# GR_Stepper_Driver.net
KiCad netlist of a schematic drawn in Altium Designer
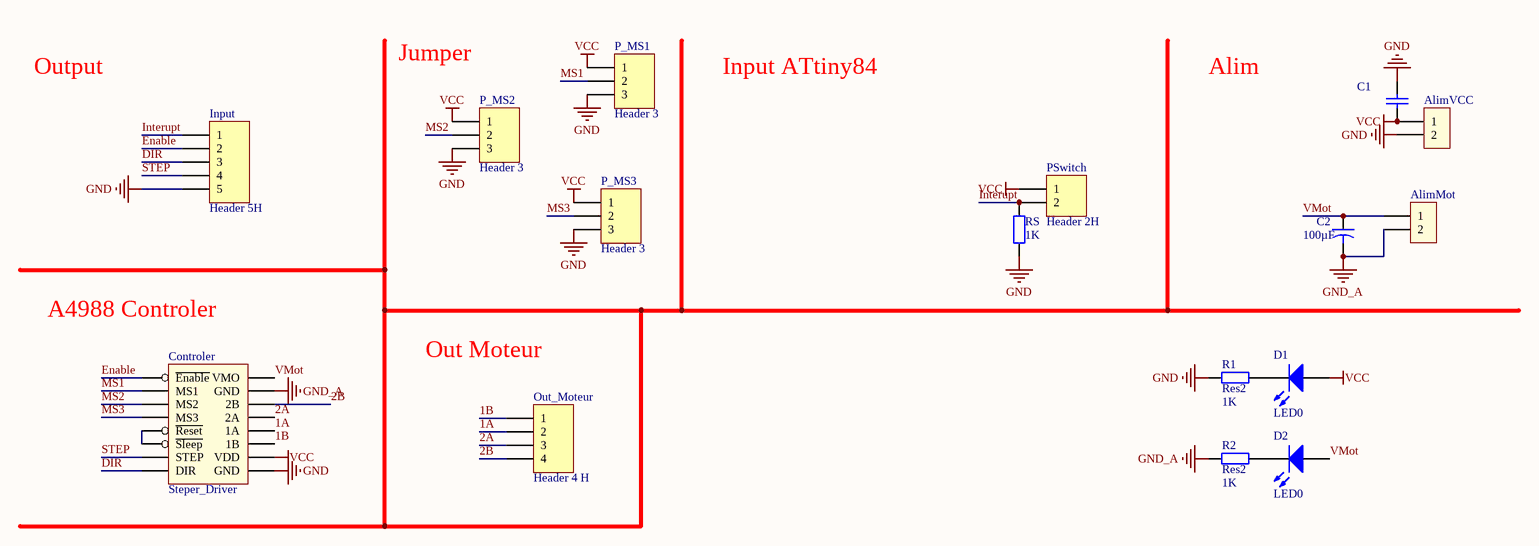
[diagram p0: GR_Stepper_Driver.SchDoc]

(export (version "E")
  (design (tool "Eeschema 10.0.6"))
  (components
    (comp (ref "AlimMot")
      (value "AlimMot")
      (footprint "Molex_MiniFitJr_2x1H")
      (libsource (lib "Robot_2019") (part "Molex_minifit_2"))
    )
    (comp (ref "AlimVCC")
      (value "AlimVCC")
      (footprint "Molex_MiniFitJr_2x1H")
      (libsource (lib "Robot_2019") (part "Molex_minifit_2"))
    )
    (comp (ref "C1")
      (value "Cap")
      (footprint "3.2X1.6X1.1")
      (description "Capacitor")
      (fields (field (name "PUBLISHER") "Altium Limited"))
      (libsource (lib "Miscellaneous Devices") (part "Cap"))
    )
    (comp (ref "C2")
      (value "100µF")
      (footprint "Robot_2019:Condensateur")
      (description "Capacitor")
      (fields (field (name "Comment") "Cap2") (field (name "PUBLISHER") "Altium Limited"))
      (libsource (lib "Miscellaneous Devices") (part "Cap2"))
    )
    (comp (ref "Controler")
      (value "Steper_Driver")
      (footprint "A4988_module")
      (description "A4988")
      (libsource (lib "Robot_2019") (part "Steper_Driver"))
    )
    (comp (ref "D1")
      (value "LED0")
      (footprint "3.2X1.6X1.1")
      (description "Typical INFRARED GaAs LED")
      (fields (field (name "PUBLISHER") "Altium Limited"))
      (libsource (lib "Miscellaneous Devices") (part "LED0"))
    )
    (comp (ref "D2")
      (value "LED0")
      (footprint "3.2X1.6X1.1")
      (description "Typical INFRARED GaAs LED")
      (fields (field (name "PUBLISHER") "Altium Limited"))
      (libsource (lib "Miscellaneous Devices") (part "LED0"))
    )
    (comp (ref "Input")
      (value "Header 5H")
      (footprint "MOLEX SPOX 5X1H")
      (description "Header, 5-Pin, Right Angle")
      (fields (field (name "PUBLISHER") "Altium Limited"))
      (libsource (lib "Miscellaneous Connectors") (part "Header 5H"))
    )
    (comp (ref "Out_Moteur")
      (value "Header 4 H")
      (footprint "Molex SPOX 4x1H")
      (description "Header, 4-Pin")
      (fields (field (name "PUBLISHER") "Altium Limited"))
      (libsource (lib "Miscellaneous Connectors") (part "Header 4"))
    )
    (comp (ref "PSwitch")
      (value "Header 2H")
      (footprint "Molex SPOX 2x1H")
      (description "Header, 2-Pin, Right Angle")
      (fields (field (name "PUBLISHER") "Altium Limited"))
      (libsource (lib "Miscellaneous Connectors") (part "Header 2H"))
    )
    (comp (ref "P_MS1")
      (value "Header 3")
      (footprint "HDR1X3")
      (description "Header, 3-Pin")
      (fields (field (name "PUBLISHER") "Altium Limited"))
      (libsource (lib "Miscellaneous Connectors") (part "Header 3"))
    )
    (comp (ref "P_MS2")
      (value "Header 3")
      (footprint "HDR1X3")
      (description "Header, 3-Pin")
      (fields (field (name "PUBLISHER") "Altium Limited"))
      (libsource (lib "Miscellaneous Connectors") (part "Header 3"))
    )
    (comp (ref "P_MS3")
      (value "Header 3")
      (footprint "HDR1X3")
      (description "Header, 3-Pin")
      (fields (field (name "PUBLISHER") "Altium Limited"))
      (libsource (lib "Miscellaneous Connectors") (part "Header 3"))
    )
    (comp (ref "R1")
      (value "Res2")
      (footprint "3.2X1.6X1.1")
      (description "Resistor")
      (fields (field (name "ALTIUM_VALUE") "1K") (field (name "PUBLISHER") "Altium Limited"))
      (libsource (lib "Miscellaneous Devices") (part "Res2"))
    )
    (comp (ref "R2")
      (value "Res2")
      (footprint "3.2X1.6X1.1")
      (description "Resistor")
      (fields (field (name "ALTIUM_VALUE") "1K") (field (name "PUBLISHER") "Altium Limited"))
      (libsource (lib "Miscellaneous Devices") (part "Res2"))
    )
    (comp (ref "RS")
      (value "1K")
      (footprint "3.2X1.6X1.1")
      (description "Resistor")
      (fields (field (name "Comment") "Res2") (field (name "PUBLISHER") "Altium Limited"))
      (libsource (lib "") (part "Res2_1"))
    )
  )
  (nets
    (net (code "1") (name "/1A") (class "Default")
      (node (ref "Controler") (pin "12") (pinfunction "1A_12") (pintype "passive"))
      (node (ref "Out_Moteur") (pin "2") (pinfunction "2_2") (pintype "passive"))
    )
    (net (code "2") (name "/1B") (class "Default")
      (node (ref "Controler") (pin "11") (pinfunction "1B_11") (pintype "passive"))
      (node (ref "Out_Moteur") (pin "1") (pinfunction "1_1") (pintype "passive"))
    )
    (net (code "3") (name "/2A") (class "Default")
      (node (ref "Controler") (pin "13") (pinfunction "2A_13") (pintype "passive"))
      (node (ref "Out_Moteur") (pin "3") (pinfunction "3_3") (pintype "passive"))
    )
    (net (code "4") (name "/2B") (class "Default")
      (node (ref "Controler") (pin "14") (pinfunction "2B_14") (pintype "passive"))
      (node (ref "Out_Moteur") (pin "4") (pinfunction "4_4") (pintype "passive"))
    )
    (net (code "7") (name "/DIR") (class "Default")
      (node (ref "Controler") (pin "8") (pinfunction "DIR_8") (pintype "passive"))
      (node (ref "Input") (pin "3") (pinfunction "3_3") (pintype "passive"))
    )
    (net (code "8") (name "/Enable") (class "Default")
      (node (ref "Controler") (pin "1") (pinfunction "~{Enable}_1") (pintype "passive"))
      (node (ref "Input") (pin "2") (pinfunction "2_2") (pintype "passive"))
    )
    (net (code "10") (name "/Interupt") (class "Default")
      (node (ref "Input") (pin "1") (pinfunction "1_1") (pintype "passive"))
      (node (ref "PSwitch") (pin "2") (pinfunction "2_2") (pintype "passive"))
      (node (ref "RS") (pin "2") (pinfunction "2_2") (pintype "passive"))
    )
    (net (code "12") (name "/MS1") (class "Default")
      (node (ref "Controler") (pin "2") (pinfunction "MS1_2") (pintype "passive"))
      (node (ref "P_MS1") (pin "2") (pinfunction "2_2") (pintype "passive"))
    )
    (net (code "13") (name "/MS2") (class "Default")
      (node (ref "Controler") (pin "3") (pinfunction "MS2_3") (pintype "passive"))
      (node (ref "P_MS2") (pin "2") (pinfunction "2_2") (pintype "passive"))
    )
    (net (code "14") (name "/MS3") (class "Default")
      (node (ref "Controler") (pin "4") (pinfunction "MS3_4") (pintype "passive"))
      (node (ref "P_MS3") (pin "2") (pinfunction "2_2") (pintype "passive"))
    )
    (net (code "17") (name "/STEP") (class "Default")
      (node (ref "Controler") (pin "7") (pinfunction "STEP_7") (pintype "passive"))
      (node (ref "Input") (pin "4") (pinfunction "4_4") (pintype "passive"))
    )
    (net (code "18") (name "/VMot") (class "Default")
      (node (ref "AlimMot") (pin "1") (pinfunction "1_1") (pintype "passive"))
      (node (ref "C2") (pin "1") (pinfunction "1_1") (pintype "passive"))
      (node (ref "Controler") (pin "16") (pinfunction "VMO_16") (pintype "passive"))
      (node (ref "D2") (pin "1") (pinfunction "A_1") (pintype "passive"))
    )
    (net (code "19") (name "GND") (class "Default")
      (node (ref "AlimVCC") (pin "2") (pinfunction "2_2") (pintype "passive"))
      (node (ref "C1") (pin "1") (pinfunction "1_1") (pintype "passive"))
      (node (ref "Controler") (pin "9") (pinfunction "GND_9") (pintype "passive"))
      (node (ref "Input") (pin "5") (pinfunction "5_5") (pintype "passive"))
      (node (ref "P_MS1") (pin "3") (pinfunction "3_3") (pintype "passive"))
      (node (ref "P_MS2") (pin "3") (pinfunction "3_3") (pintype "passive"))
      (node (ref "P_MS3") (pin "3") (pinfunction "3_3") (pintype "passive"))
      (node (ref "R1") (pin "1") (pinfunction "1_1") (pintype "passive"))
      (node (ref "RS") (pin "1") (pinfunction "1_1") (pintype "passive"))
    )
    (net (code "20") (name "GND_A") (class "Default")
      (node (ref "AlimMot") (pin "2") (pinfunction "2_2") (pintype "passive"))
      (node (ref "C2") (pin "2") (pinfunction "2_2") (pintype "passive"))
      (node (ref "Controler") (pin "15") (pinfunction "GND_15") (pintype "passive"))
      (node (ref "R2") (pin "1") (pinfunction "1_1") (pintype "passive"))
    )
    (net (code "21") (name "Net-(Controler-~{Reset})") (class "Default")
      (node (ref "Controler") (pin "5") (pinfunction "~{Reset}_5") (pintype "passive"))
      (node (ref "Controler") (pin "6") (pinfunction "~{Sleep}_6") (pintype "passive"))
    )
    (net (code "22") (name "Net-(D1-K)") (class "Default")
      (node (ref "D1") (pin "2") (pinfunction "K_2") (pintype "passive"))
      (node (ref "R1") (pin "2") (pinfunction "2_2") (pintype "passive"))
    )
    (net (code "23") (name "Net-(D2-K)") (class "Default")
      (node (ref "D2") (pin "2") (pinfunction "K_2") (pintype "passive"))
      (node (ref "R2") (pin "2") (pinfunction "2_2") (pintype "passive"))
    )
    (net (code "24") (name "VCC") (class "Default")
      (node (ref "AlimVCC") (pin "1") (pinfunction "1_1") (pintype "passive"))
      (node (ref "C1") (pin "2") (pinfunction "2_2") (pintype "passive"))
      (node (ref "Controler") (pin "10") (pinfunction "VDD_10") (pintype "passive"))
      (node (ref "D1") (pin "1") (pinfunction "A_1") (pintype "passive"))
      (node (ref "PSwitch") (pin "1") (pinfunction "1_1") (pintype "passive"))
      (node (ref "P_MS1") (pin "1") (pinfunction "1_1") (pintype "passive"))
      (node (ref "P_MS2") (pin "1") (pinfunction "1_1") (pintype "passive"))
      (node (ref "P_MS3") (pin "1") (pinfunction "1_1") (pintype "passive"))
    )
  )
)
